# PCC_LED_Badge_v01.net
KiCad netlist of a schematic drawn in EAGLE
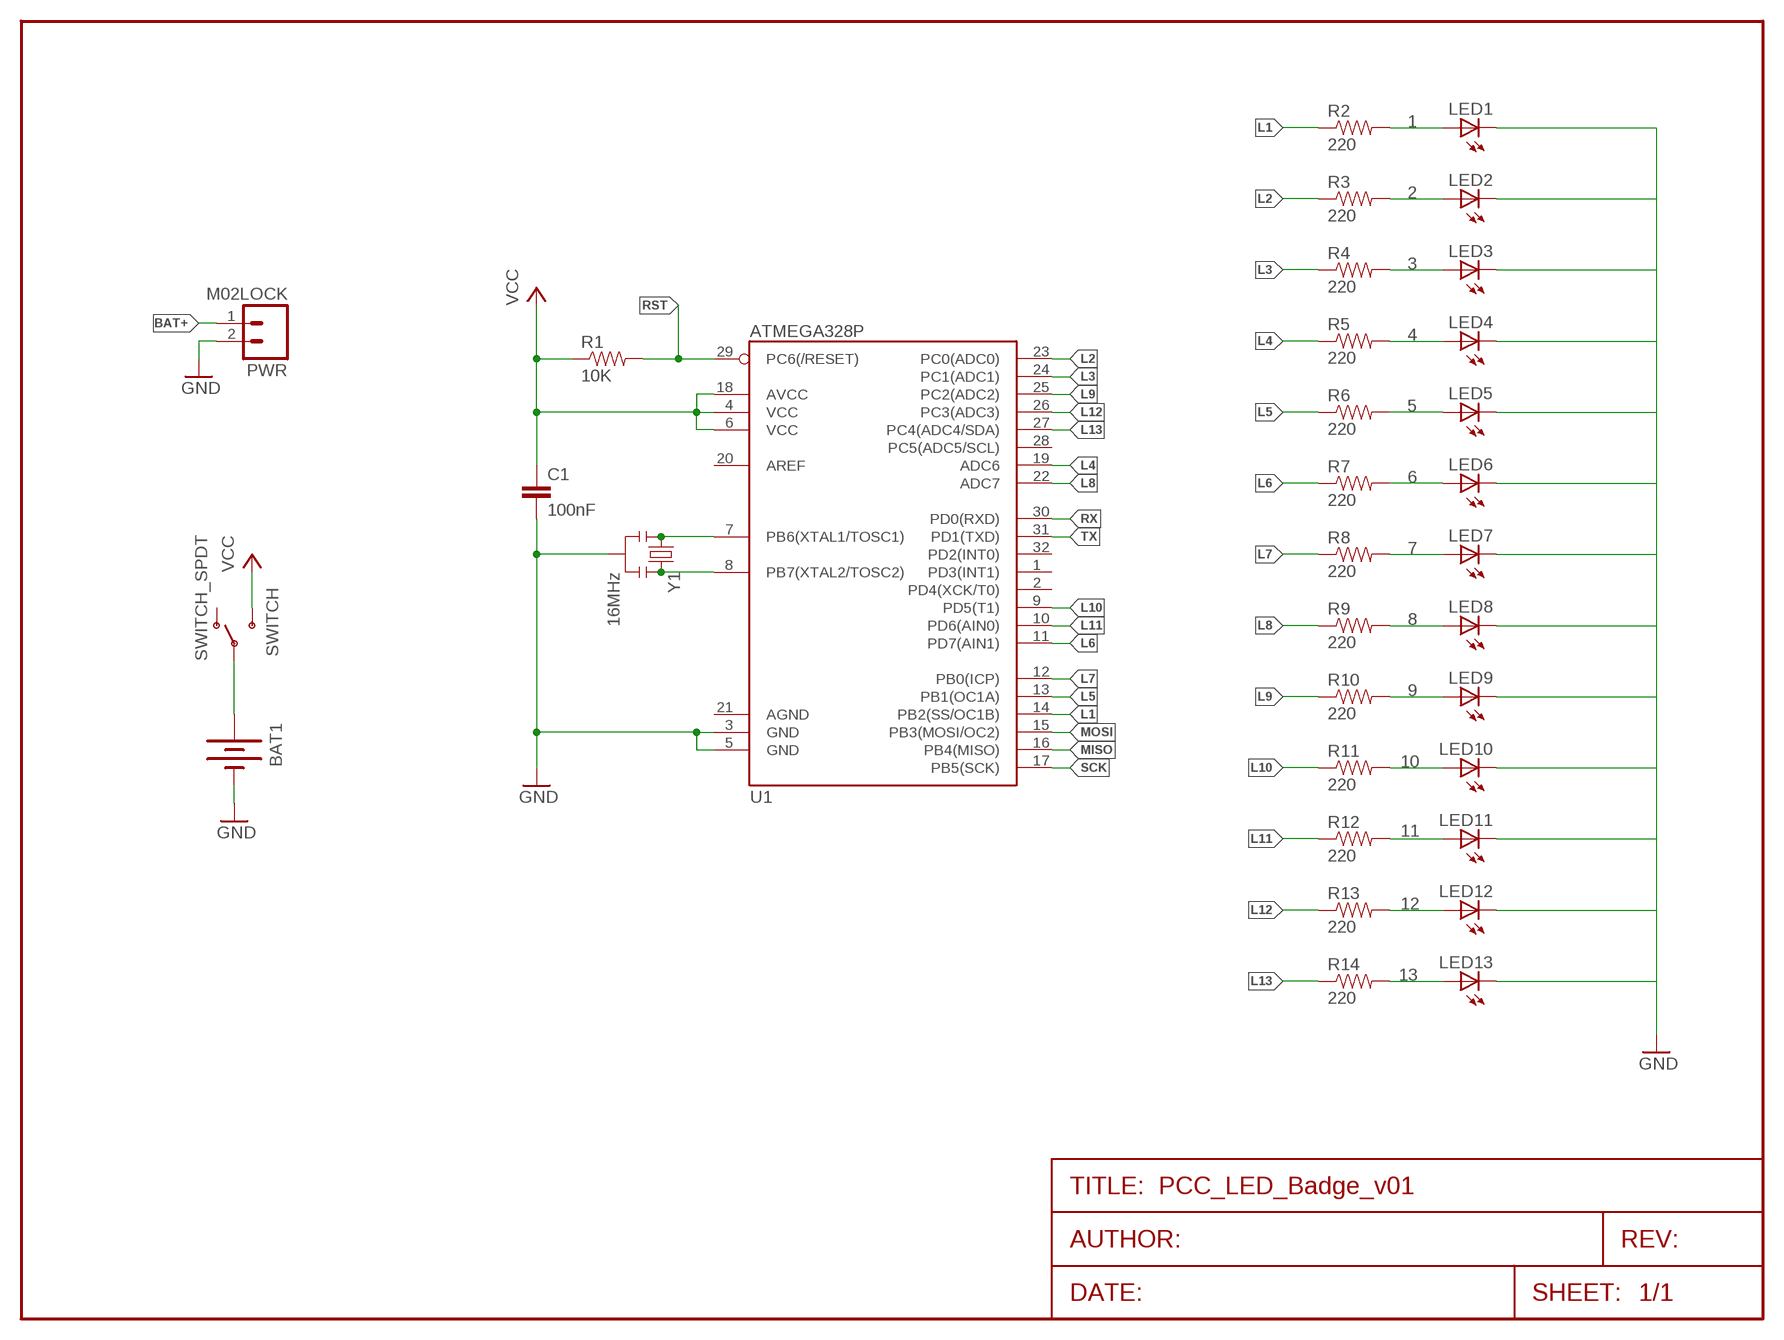
[diagram p0: schematic, sheet 1]

(export (version "E")
  (design (tool "Eeschema 10.0.6"))
  (components
    (comp (ref "BAT1")
      (value "BATTERY20SMD")
      (footprint "eagle-import:BATTCON_20MM")
      (libsource (lib "eagle-import") (part "BATTERY20SMD"))
    )
    (comp (ref "C1")
      (value "100nF")
      (footprint "eagle-import:0603-CAP")
      (libsource (lib "eagle-import") (part "CAP0603-CAP"))
    )
    (comp (ref "LED1")
      (value "LED0603")
      (footprint "eagle-import:LED-0603")
      (libsource (lib "eagle-import") (part "LED0603"))
    )
    (comp (ref "LED2")
      (value "LED0603")
      (footprint "eagle-import:LED-0603")
      (libsource (lib "eagle-import") (part "LED0603"))
    )
    (comp (ref "LED3")
      (value "LED0603")
      (footprint "eagle-import:LED-0603")
      (libsource (lib "eagle-import") (part "LED0603"))
    )
    (comp (ref "LED4")
      (value "LED0603")
      (footprint "eagle-import:LED-0603")
      (libsource (lib "eagle-import") (part "LED0603"))
    )
    (comp (ref "LED5")
      (value "LED0603")
      (footprint "eagle-import:LED-0603")
      (libsource (lib "eagle-import") (part "LED0603"))
    )
    (comp (ref "LED6")
      (value "LED0603")
      (footprint "eagle-import:LED-0603")
      (libsource (lib "eagle-import") (part "LED0603"))
    )
    (comp (ref "LED7")
      (value "LED0603")
      (footprint "eagle-import:LED-0603")
      (libsource (lib "eagle-import") (part "LED0603"))
    )
    (comp (ref "LED8")
      (value "LED0603")
      (footprint "eagle-import:LED-0603")
      (libsource (lib "eagle-import") (part "LED0603"))
    )
    (comp (ref "LED9")
      (value "LED0603")
      (footprint "eagle-import:LED-0603")
      (libsource (lib "eagle-import") (part "LED0603"))
    )
    (comp (ref "LED10")
      (value "LED0603")
      (footprint "eagle-import:LED-0603")
      (libsource (lib "eagle-import") (part "LED0603"))
    )
    (comp (ref "LED11")
      (value "LED0603")
      (footprint "eagle-import:LED-0603")
      (libsource (lib "eagle-import") (part "LED0603"))
    )
    (comp (ref "LED12")
      (value "LED0603")
      (footprint "eagle-import:LED-0603")
      (libsource (lib "eagle-import") (part "LED0603"))
    )
    (comp (ref "LED13")
      (value "LED0603")
      (footprint "eagle-import:LED-0603")
      (libsource (lib "eagle-import") (part "LED0603"))
    )
    (comp (ref "PWR")
      (value "M02LOCK")
      (footprint "eagle-import:1X02_LOCK")
      (libsource (lib "eagle-import") (part "M02LOCK"))
    )
    (comp (ref "R1")
      (value "10K")
      (footprint "eagle-import:0603-RES")
      (libsource (lib "eagle-import") (part "RESISTOR0603-RES"))
    )
    (comp (ref "R2")
      (value "220")
      (footprint "eagle-import:0603-RES")
      (libsource (lib "eagle-import") (part "RESISTOR0603-RES"))
    )
    (comp (ref "R3")
      (value "220")
      (footprint "eagle-import:0603-RES")
      (libsource (lib "eagle-import") (part "RESISTOR0603-RES"))
    )
    (comp (ref "R4")
      (value "220")
      (footprint "eagle-import:0603-RES")
      (libsource (lib "eagle-import") (part "RESISTOR0603-RES"))
    )
    (comp (ref "R5")
      (value "220")
      (footprint "eagle-import:0603-RES")
      (libsource (lib "eagle-import") (part "RESISTOR0603-RES"))
    )
    (comp (ref "R6")
      (value "220")
      (footprint "eagle-import:0603-RES")
      (libsource (lib "eagle-import") (part "RESISTOR0603-RES"))
    )
    (comp (ref "R7")
      (value "220")
      (footprint "eagle-import:0603-RES")
      (libsource (lib "eagle-import") (part "RESISTOR0603-RES"))
    )
    (comp (ref "R8")
      (value "220")
      (footprint "eagle-import:0603-RES")
      (libsource (lib "eagle-import") (part "RESISTOR0603-RES"))
    )
    (comp (ref "R9")
      (value "220")
      (footprint "eagle-import:0603-RES")
      (libsource (lib "eagle-import") (part "RESISTOR0603-RES"))
    )
    (comp (ref "R10")
      (value "220")
      (footprint "eagle-import:0603-RES")
      (libsource (lib "eagle-import") (part "RESISTOR0603-RES"))
    )
    (comp (ref "R11")
      (value "220")
      (footprint "eagle-import:0603-RES")
      (libsource (lib "eagle-import") (part "RESISTOR0603-RES"))
    )
    (comp (ref "R12")
      (value "220")
      (footprint "eagle-import:0603-RES")
      (libsource (lib "eagle-import") (part "RESISTOR0603-RES"))
    )
    (comp (ref "R13")
      (value "220")
      (footprint "eagle-import:0603-RES")
      (libsource (lib "eagle-import") (part "RESISTOR0603-RES"))
    )
    (comp (ref "R14")
      (value "220")
      (footprint "eagle-import:0603-RES")
      (libsource (lib "eagle-import") (part "RESISTOR0603-RES"))
    )
    (comp (ref "SWITCH")
      (value "SWITCH_SPDT")
      (footprint "eagle-import:KPS-1290")
      (libsource (lib "eagle-import") (part "SWITCH_SPDT"))
    )
    (comp (ref "U1")
      (value "ATMEGA328P")
      (footprint "eagle-import:TQFP32-08")
      (libsource (lib "eagle-import") (part "ATMEGA328_SMT"))
    )
    (comp (ref "Y1")
      (value "16MHz")
      (footprint "eagle-import:RESONATOR-SMD")
      (libsource (lib "eagle-import") (part "RESONATOR16MHZ"))
    )
  )
  (nets
    (net (code "1") (name "/1") (class "Default")
      (node (ref "LED1") (pin "A") (pinfunction "A_A") (pintype "passive"))
      (node (ref "R2") (pin "2") (pinfunction "2_2") (pintype "passive"))
    )
    (net (code "2") (name "/2") (class "Default")
      (node (ref "LED2") (pin "A") (pinfunction "A_A") (pintype "passive"))
      (node (ref "R3") (pin "2") (pinfunction "2_2") (pintype "passive"))
    )
    (net (code "3") (name "/3") (class "Default")
      (node (ref "LED3") (pin "A") (pinfunction "A_A") (pintype "passive"))
      (node (ref "R4") (pin "2") (pinfunction "2_2") (pintype "passive"))
    )
    (net (code "4") (name "/4") (class "Default")
      (node (ref "LED4") (pin "A") (pinfunction "A_A") (pintype "passive"))
      (node (ref "R5") (pin "2") (pinfunction "2_2") (pintype "passive"))
    )
    (net (code "5") (name "/5") (class "Default")
      (node (ref "LED5") (pin "A") (pinfunction "A_A") (pintype "passive"))
      (node (ref "R6") (pin "2") (pinfunction "2_2") (pintype "passive"))
    )
    (net (code "6") (name "/6") (class "Default")
      (node (ref "LED6") (pin "A") (pinfunction "A_A") (pintype "passive"))
      (node (ref "R7") (pin "2") (pinfunction "2_2") (pintype "passive"))
    )
    (net (code "7") (name "/7") (class "Default")
      (node (ref "LED7") (pin "A") (pinfunction "A_A") (pintype "passive"))
      (node (ref "R8") (pin "2") (pinfunction "2_2") (pintype "passive"))
    )
    (net (code "8") (name "/8") (class "Default")
      (node (ref "LED8") (pin "A") (pinfunction "A_A") (pintype "passive"))
      (node (ref "R9") (pin "2") (pinfunction "2_2") (pintype "passive"))
    )
    (net (code "9") (name "/9") (class "Default")
      (node (ref "LED9") (pin "A") (pinfunction "A_A") (pintype "passive"))
      (node (ref "R10") (pin "2") (pinfunction "2_2") (pintype "passive"))
    )
    (net (code "10") (name "/10") (class "Default")
      (node (ref "LED10") (pin "A") (pinfunction "A_A") (pintype "passive"))
      (node (ref "R11") (pin "2") (pinfunction "2_2") (pintype "passive"))
    )
    (net (code "11") (name "/11") (class "Default")
      (node (ref "LED11") (pin "A") (pinfunction "A_A") (pintype "passive"))
      (node (ref "R12") (pin "2") (pinfunction "2_2") (pintype "passive"))
    )
    (net (code "12") (name "/12") (class "Default")
      (node (ref "LED12") (pin "A") (pinfunction "A_A") (pintype "passive"))
      (node (ref "R13") (pin "2") (pinfunction "2_2") (pintype "passive"))
    )
    (net (code "13") (name "/13") (class "Default")
      (node (ref "LED13") (pin "A") (pinfunction "A_A") (pintype "passive"))
      (node (ref "R14") (pin "2") (pinfunction "2_2") (pintype "passive"))
    )
    (net (code "14") (name "BAT+") (class "Default")
      (node (ref "BAT1") (pin "1") (pinfunction "+_1") (pintype "power_in"))
      (node (ref "PWR") (pin "1") (pinfunction "1_1") (pintype "passive"))
      (node (ref "SWITCH") (pin "P") (pinfunction "P_P") (pintype "passive"))
    )
    (net (code "15") (name "GND") (class "Default")
      (node (ref "BAT1") (pin "2") (pinfunction "-_2") (pintype "power_in"))
      (node (ref "C1") (pin "2") (pinfunction "2_2") (pintype "passive"))
      (node (ref "LED1") (pin "C") (pinfunction "C_C") (pintype "passive"))
      (node (ref "LED10") (pin "C") (pinfunction "C_C") (pintype "passive"))
      (node (ref "LED11") (pin "C") (pinfunction "C_C") (pintype "passive"))
      (node (ref "LED12") (pin "C") (pinfunction "C_C") (pintype "passive"))
      (node (ref "LED13") (pin "C") (pinfunction "C_C") (pintype "passive"))
      (node (ref "LED2") (pin "C") (pinfunction "C_C") (pintype "passive"))
      (node (ref "LED3") (pin "C") (pinfunction "C_C") (pintype "passive"))
      (node (ref "LED4") (pin "C") (pinfunction "C_C") (pintype "passive"))
      (node (ref "LED5") (pin "C") (pinfunction "C_C") (pintype "passive"))
      (node (ref "LED6") (pin "C") (pinfunction "C_C") (pintype "passive"))
      (node (ref "LED7") (pin "C") (pinfunction "C_C") (pintype "passive"))
      (node (ref "LED8") (pin "C") (pinfunction "C_C") (pintype "passive"))
      (node (ref "LED9") (pin "C") (pinfunction "C_C") (pintype "passive"))
      (node (ref "PWR") (pin "2") (pinfunction "2_2") (pintype "passive"))
      (node (ref "U1") (pin "3") (pinfunction "GND_3") (pintype "bidirectional"))
      (node (ref "U1") (pin "5") (pinfunction "GND_5") (pintype "bidirectional"))
      (node (ref "Y1") (pin "2") (pinfunction "2_2") (pintype "passive"))
    )
    (net (code "16") (name "L1") (class "Default")
      (node (ref "R2") (pin "1") (pinfunction "1_1") (pintype "passive"))
      (node (ref "U1") (pin "14") (pinfunction "PB2(SS/OC1B)_14") (pintype "bidirectional"))
    )
    (net (code "17") (name "L2") (class "Default")
      (node (ref "R3") (pin "1") (pinfunction "1_1") (pintype "passive"))
      (node (ref "U1") (pin "23") (pinfunction "PC0(ADC0)_23") (pintype "bidirectional"))
    )
    (net (code "18") (name "L3") (class "Default")
      (node (ref "R4") (pin "1") (pinfunction "1_1") (pintype "passive"))
      (node (ref "U1") (pin "24") (pinfunction "PC1(ADC1)_24") (pintype "bidirectional"))
    )
    (net (code "19") (name "L4") (class "Default")
      (node (ref "R5") (pin "1") (pinfunction "1_1") (pintype "passive"))
      (node (ref "U1") (pin "19") (pinfunction "ADC6_19") (pintype "bidirectional"))
    )
    (net (code "20") (name "L5") (class "Default")
      (node (ref "R6") (pin "1") (pinfunction "1_1") (pintype "passive"))
      (node (ref "U1") (pin "13") (pinfunction "PB1(OC1A)_13") (pintype "bidirectional"))
    )
    (net (code "21") (name "L6") (class "Default")
      (node (ref "R7") (pin "1") (pinfunction "1_1") (pintype "passive"))
      (node (ref "U1") (pin "11") (pinfunction "PD7(AIN1)_11") (pintype "bidirectional"))
    )
    (net (code "22") (name "L7") (class "Default")
      (node (ref "R8") (pin "1") (pinfunction "1_1") (pintype "passive"))
      (node (ref "U1") (pin "12") (pinfunction "PB0(ICP)_12") (pintype "bidirectional"))
    )
    (net (code "23") (name "L8") (class "Default")
      (node (ref "R9") (pin "1") (pinfunction "1_1") (pintype "passive"))
      (node (ref "U1") (pin "22") (pinfunction "ADC7_22") (pintype "bidirectional"))
    )
    (net (code "24") (name "L9") (class "Default")
      (node (ref "R10") (pin "1") (pinfunction "1_1") (pintype "passive"))
      (node (ref "U1") (pin "25") (pinfunction "PC2(ADC2)_25") (pintype "bidirectional"))
    )
    (net (code "25") (name "L10") (class "Default")
      (node (ref "R11") (pin "1") (pinfunction "1_1") (pintype "passive"))
      (node (ref "U1") (pin "9") (pinfunction "PD5(T1)_9") (pintype "bidirectional"))
    )
    (net (code "26") (name "L11") (class "Default")
      (node (ref "R12") (pin "1") (pinfunction "1_1") (pintype "passive"))
      (node (ref "U1") (pin "10") (pinfunction "PD6(AIN0)_10") (pintype "bidirectional"))
    )
    (net (code "27") (name "L12") (class "Default")
      (node (ref "R13") (pin "1") (pinfunction "1_1") (pintype "passive"))
      (node (ref "U1") (pin "26") (pinfunction "PC3(ADC3)_26") (pintype "bidirectional"))
    )
    (net (code "28") (name "L13") (class "Default")
      (node (ref "R14") (pin "1") (pinfunction "1_1") (pintype "passive"))
      (node (ref "U1") (pin "27") (pinfunction "PC4(ADC4/SDA)_27") (pintype "bidirectional"))
    )
    (net (code "29") (name "MISO") (class "Default")
      (node (ref "U1") (pin "16") (pinfunction "PB4(MISO)_16") (pintype "bidirectional"))
    )
    (net (code "30") (name "MOSI") (class "Default")
      (node (ref "U1") (pin "15") (pinfunction "PB3(MOSI/OC2)_15") (pintype "bidirectional"))
    )
    (net (code "31") (name "Net-(U1-PB6(XTAL1{slash}TOSC1))") (class "Default")
      (node (ref "U1") (pin "7") (pinfunction "PB6(XTAL1/TOSC1)_7") (pintype "bidirectional"))
      (node (ref "Y1") (pin "1") (pinfunction "1_1") (pintype "passive"))
    )
    (net (code "32") (name "Net-(U1-PB7(XTAL2{slash}TOSC2))") (class "Default")
      (node (ref "U1") (pin "8") (pinfunction "PB7(XTAL2/TOSC2)_8") (pintype "bidirectional"))
      (node (ref "Y1") (pin "3") (pinfunction "3_3") (pintype "passive"))
    )
    (net (code "33") (name "RST") (class "Default")
      (node (ref "R1") (pin "2") (pinfunction "2_2") (pintype "passive"))
      (node (ref "U1") (pin "29") (pinfunction "PC6(/RESET)_29") (pintype "bidirectional"))
    )
    (net (code "34") (name "RX") (class "Default")
      (node (ref "U1") (pin "30") (pinfunction "PD0(RXD)_30") (pintype "bidirectional"))
    )
    (net (code "35") (name "SCK") (class "Default")
      (node (ref "U1") (pin "17") (pinfunction "PB5(SCK)_17") (pintype "bidirectional"))
    )
    (net (code "36") (name "TX") (class "Default")
      (node (ref "U1") (pin "31") (pinfunction "PD1(TXD)_31") (pintype "bidirectional"))
    )
    (net (code "37") (name "VCC") (class "Default")
      (node (ref "C1") (pin "1") (pinfunction "1_1") (pintype "passive"))
      (node (ref "R1") (pin "1") (pinfunction "1_1") (pintype "passive"))
      (node (ref "SWITCH") (pin "S") (pinfunction "S_S") (pintype "passive"))
      (node (ref "U1") (pin "18") (pinfunction "AVCC_18") (pintype "bidirectional"))
      (node (ref "U1") (pin "4") (pinfunction "VCC_4") (pintype "bidirectional"))
      (node (ref "U1") (pin "6") (pinfunction "VCC_6") (pintype "bidirectional"))
    )
    (net (code "38") (name "unconnected-(SWITCH-PadO)") (class "Default")
      (node (ref "SWITCH") (pin "O") (pinfunction "O_O") (pintype "passive"))
    )
    (net (code "39") (name "unconnected-(U1-AGND-Pad21)") (class "Default")
      (node (ref "U1") (pin "21") (pinfunction "AGND_21") (pintype "bidirectional"))
    )
    (net (code "40") (name "unconnected-(U1-AREF-Pad20)") (class "Default")
      (node (ref "U1") (pin "20") (pinfunction "AREF_20") (pintype "bidirectional"))
    )
    (net (code "41") (name "unconnected-(U1-PC5(ADC5{slash}SCL)-Pad28)") (class "Default")
      (node (ref "U1") (pin "28") (pinfunction "PC5(ADC5/SCL)_28") (pintype "bidirectional"))
    )
    (net (code "42") (name "unconnected-(U1-PD2(INT0)-Pad32)") (class "Default")
      (node (ref "U1") (pin "32") (pinfunction "PD2(INT0)_32") (pintype "bidirectional"))
    )
    (net (code "43") (name "unconnected-(U1-PD3(INT1)-Pad1)") (class "Default")
      (node (ref "U1") (pin "1") (pinfunction "PD3(INT1)_1") (pintype "bidirectional"))
    )
    (net (code "44") (name "unconnected-(U1-PD4(XCK{slash}T0)-Pad2)") (class "Default")
      (node (ref "U1") (pin "2") (pinfunction "PD4(XCK/T0)_2") (pintype "bidirectional"))
    )
  )
)
